# sol_sens.net
KiCad netlist of a schematic drawn in EAGLE
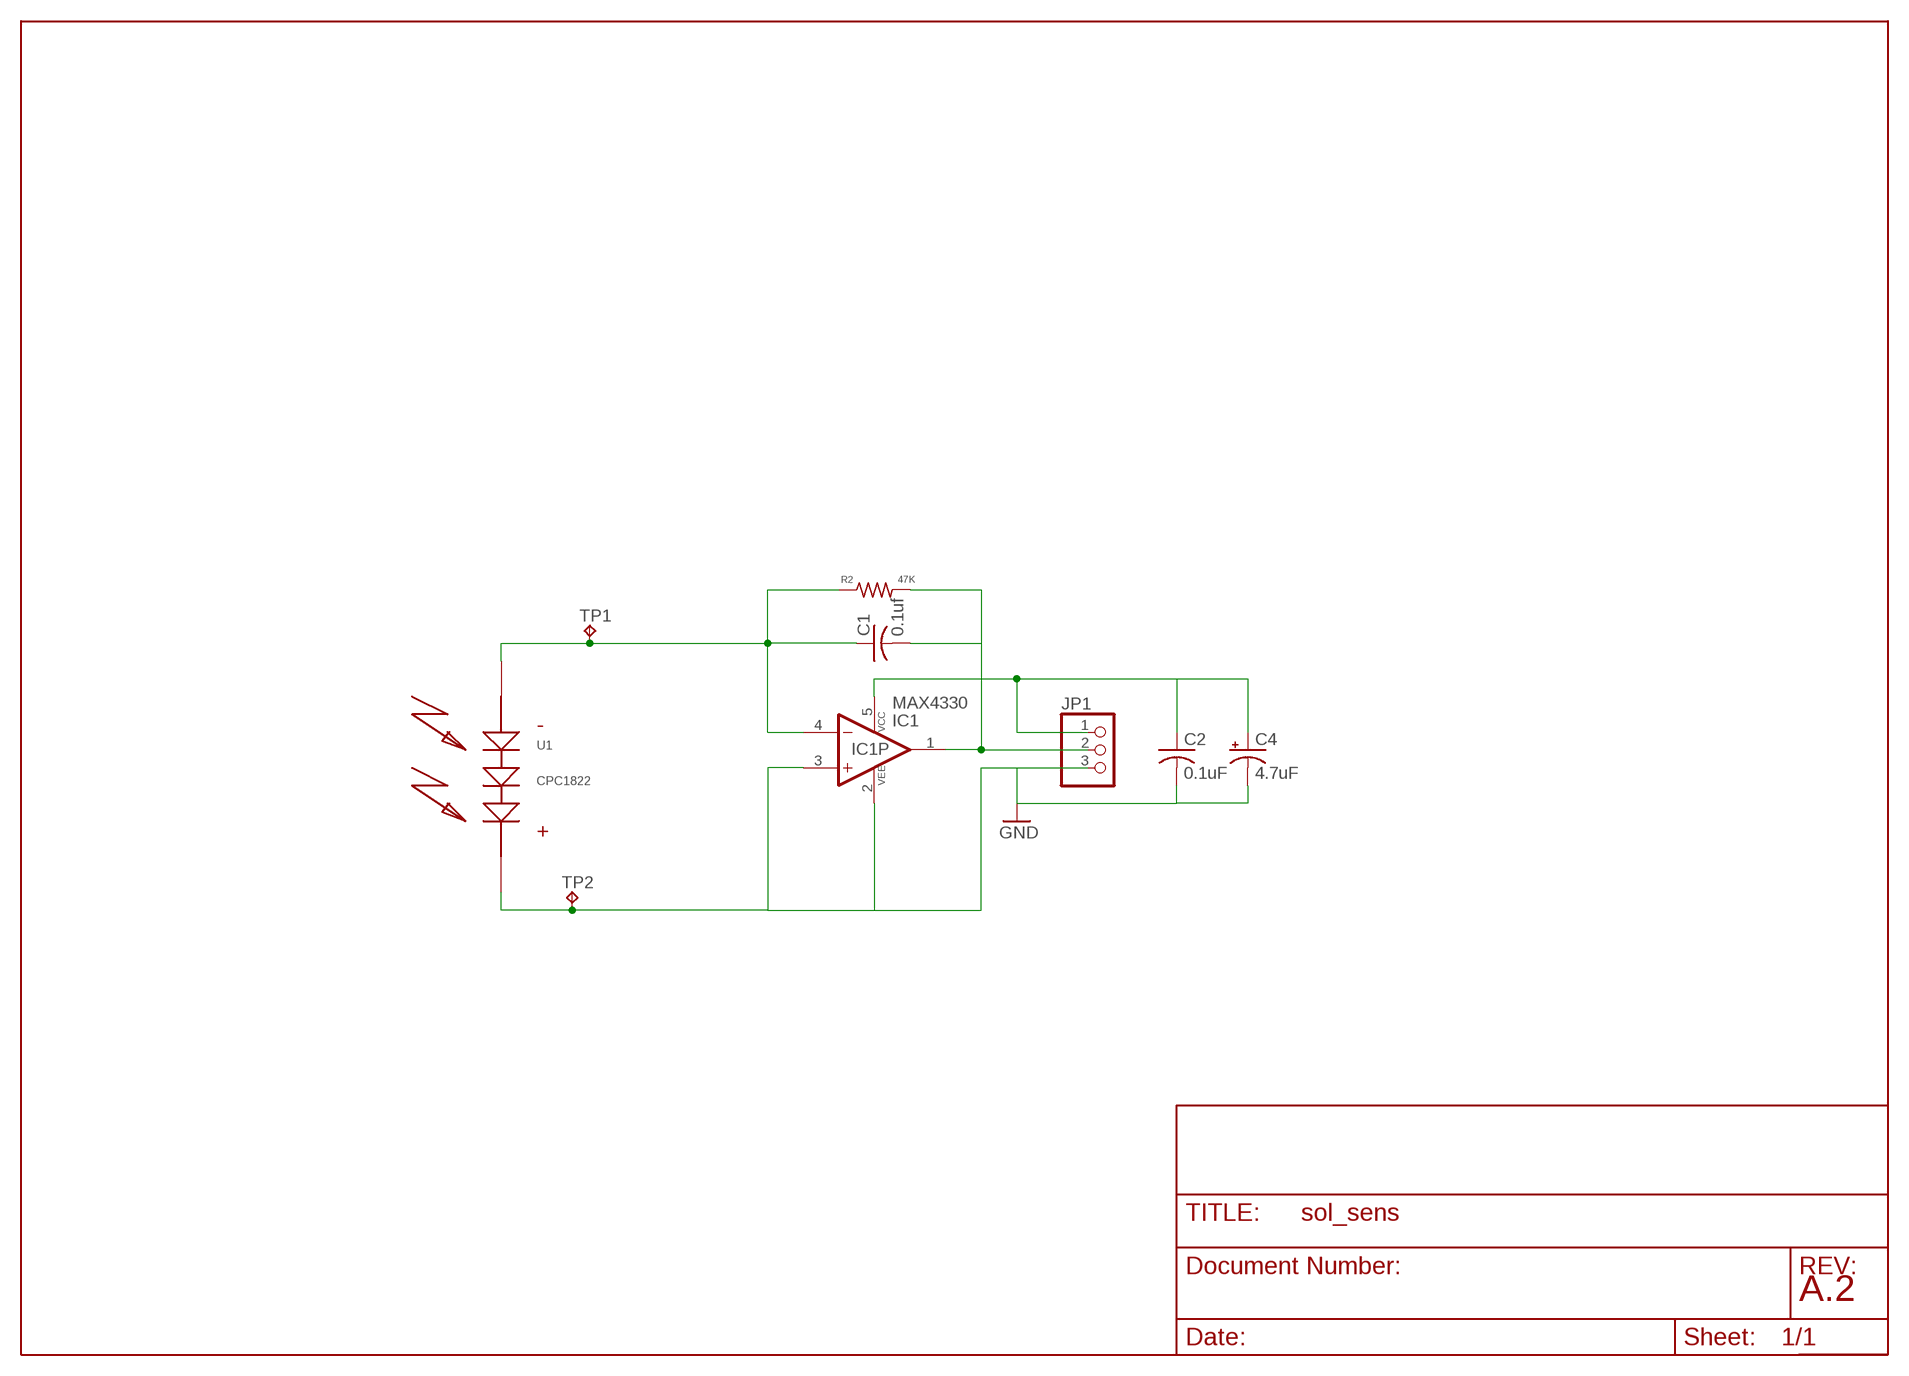
[diagram p0: schematic, sheet 1]

(export (version "E")
  (design (tool "Eeschema 10.0.6"))
  (components
    (comp (ref "C1")
      (value "0.1uf")
      (footprint "eagle-import:C0805")
      (libsource (lib "eagle-import") (part "C-USC0805"))
    )
    (comp (ref "C2")
      (value "0.1uF")
      (footprint "eagle-import:C0805")
      (libsource (lib "eagle-import") (part "C-USC0805"))
    )
    (comp (ref "C4")
      (value "4.7uF")
      (footprint "eagle-import:R_2012-12R")
      (libsource (lib "eagle-import") (part "CPOL-USR/2012-12R"))
    )
    (comp (ref "IC1")
      (value "MAX4330")
      (footprint "eagle-import:SOT23-5")
      (libsource (lib "eagle-import") (part "MAX4330"))
    )
    (comp (ref "JP1")
      (value "PINHD-1X3")
      (footprint "eagle-import:1X03")
      (libsource (lib "eagle-import") (part "PINHD-1X3"))
    )
    (comp (ref "R2")
      (value "47K")
      (footprint "eagle-import:R0805")
      (libsource (lib "eagle-import") (part "R-US_R0805"))
    )
    (comp (ref "TP1")
      (value "TPB1,27")
      (footprint "eagle-import:B1,27")
      (libsource (lib "eagle-import") (part "TPB1,27"))
    )
    (comp (ref "TP2")
      (value "TPB1,27")
      (footprint "eagle-import:B1,27")
      (libsource (lib "eagle-import") (part "TPB1,27"))
    )
    (comp (ref "U1")
      (value "CPC1822")
      (footprint "eagle-import:SO08")
      (libsource (lib "eagle-import") (part "CPC1822"))
    )
  )
  (nets
    (net (code "1") (name "GND") (class "Default")
      (node (ref "C2") (pin "2") (pinfunction "2_2") (pintype "passive"))
      (node (ref "C4") (pin "-") (pinfunction "-_-") (pintype "passive"))
      (node (ref "IC1") (pin "2") (pinfunction "VEE_2") (pintype "power_in"))
      (node (ref "IC1") (pin "3") (pinfunction "+IN_3") (pintype "input"))
      (node (ref "JP1") (pin "3") (pinfunction "3_3") (pintype "passive"))
      (node (ref "TP2") (pin "PP") (pinfunction "TP_PP") (pintype "input"))
      (node (ref "U1") (pin "8") (pinfunction "V+_8") (pintype "bidirectional"))
    )
    (net (code "2") (name "Net-(IC1A--IN)") (class "Default")
      (node (ref "C1") (pin "1") (pinfunction "1_1") (pintype "passive"))
      (node (ref "IC1") (pin "4") (pinfunction "-IN_4") (pintype "input"))
      (node (ref "R2") (pin "1") (pinfunction "1_1") (pintype "passive"))
      (node (ref "TP1") (pin "PP") (pinfunction "TP_PP") (pintype "input"))
      (node (ref "U1") (pin "5") (pinfunction "V-_5") (pintype "bidirectional"))
    )
    (net (code "3") (name "Net-(IC1A-OUT)") (class "Default")
      (node (ref "C1") (pin "2") (pinfunction "2_2") (pintype "passive"))
      (node (ref "IC1") (pin "1") (pinfunction "OUT_1") (pintype "output"))
      (node (ref "JP1") (pin "2") (pinfunction "2_2") (pintype "passive"))
      (node (ref "R2") (pin "2") (pinfunction "2_2") (pintype "passive"))
    )
    (net (code "4") (name "Net-(IC1B-VCC)") (class "Default")
      (node (ref "C2") (pin "1") (pinfunction "1_1") (pintype "passive"))
      (node (ref "C4") (pin "+") (pinfunction "+_+") (pintype "passive"))
      (node (ref "IC1") (pin "5") (pinfunction "VCC_5") (pintype "power_in"))
      (node (ref "JP1") (pin "1") (pinfunction "1_1") (pintype "passive"))
    )
  )
)
